# V2_SkyLight.net
KiCad netlist of a schematic drawn in Altium Designer
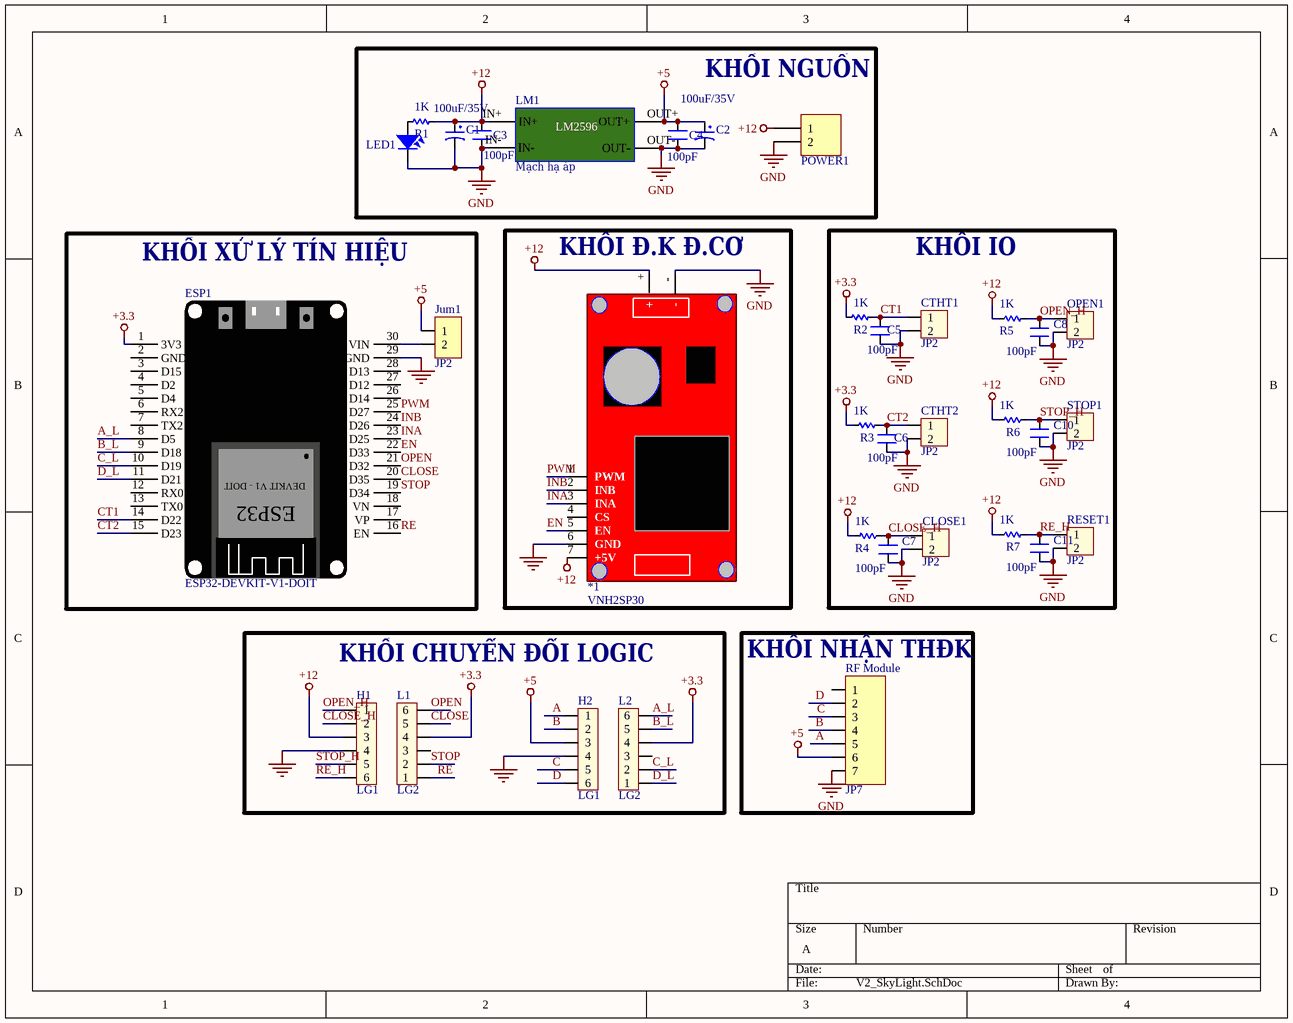
[diagram p0: V2_SkyLight.SchDoc]

(export (version "E")
  (design (tool "Eeschema 10.0.6"))
  (components
    (comp (ref "*1")
      (value "VNH2SP30")
      (footprint "VNH2SP30")
      (libsource (lib "Nhuphung_Main") (part "VNH2SP30"))
    )
    (comp (ref "C1")
      (value "100uF/35V")
      (footprint "CP1.5/3.4")
      (description "Cap 100uF/35V - 470uF/16V")
      (libsource (lib "syhaunguyen") (part "CP3"))
    )
    (comp (ref "C2")
      (value "100uF/35V")
      (footprint "CP1.5/3.4")
      (description "Cap 100uF/35V - 470uF/16V")
      (libsource (lib "syhaunguyen") (part "CP3"))
    )
    (comp (ref "C3")
      (value "100pF")
      (footprint "CN1")
      (description "Cap np  1pF - 472pF")
      (libsource (lib "syhaunguyen") (part "CN1"))
    )
    (comp (ref "C4")
      (value "100pF")
      (footprint "CN1")
      (description "Cap np  1pF - 472pF")
      (libsource (lib "syhaunguyen") (part "CN1"))
    )
    (comp (ref "C5")
      (value "100pF")
      (footprint "CN1")
      (description "Cap np  1pF - 472pF")
      (libsource (lib "syhaunguyen") (part "CN1"))
    )
    (comp (ref "C6")
      (value "100pF")
      (footprint "CN1")
      (description "Cap np  1pF - 472pF")
      (libsource (lib "syhaunguyen") (part "CN1"))
    )
    (comp (ref "C7")
      (value "100pF")
      (footprint "CN1")
      (description "Cap np  1pF - 472pF")
      (libsource (lib "syhaunguyen") (part "CN1"))
    )
    (comp (ref "C8")
      (value "100pF")
      (footprint "CN1")
      (description "Cap np  1pF - 472pF")
      (libsource (lib "syhaunguyen") (part "CN1"))
    )
    (comp (ref "C10")
      (value "100pF")
      (footprint "CN1")
      (description "Cap np  1pF - 472pF")
      (libsource (lib "syhaunguyen") (part "CN1"))
    )
    (comp (ref "C11")
      (value "100pF")
      (footprint "CN1")
      (description "Cap np  1pF - 472pF")
      (libsource (lib "syhaunguyen") (part "CN1"))
    )
    (comp (ref "CLOSE1")
      (value "JP2")
      (footprint "CON2")
      (description "Connector 2")
      (libsource (lib "syhaunguyen") (part "Con2"))
    )
    (comp (ref "CTHT1")
      (value "JP2")
      (footprint "CON2")
      (description "Connector 2")
      (libsource (lib "syhaunguyen") (part "Con2"))
    )
    (comp (ref "CTHT2")
      (value "JP2")
      (footprint "CON2")
      (description "Connector 2")
      (libsource (lib "syhaunguyen") (part "Con2"))
    )
    (comp (ref "ESP1")
      (value "ESP32-DEVKIT-V1-DOIT")
      (footprint "ESP32-WROOM-32")
      (libsource (lib "Nhuphung_Main") (part "ESP32-DEVKIT-V1-DOIT"))
    )
    (comp (ref "H1")
      (value "LG1")
      (footprint "JP6")
      (description "JP6 PIN")
      (libsource (lib "syhaunguyen") (part "JP6"))
    )
    (comp (ref "H2")
      (value "LG1")
      (footprint "JP6")
      (description "JP6 PIN")
      (libsource (lib "syhaunguyen") (part "JP6"))
    )
    (comp (ref "Jum1")
      (value "JP2")
      (footprint "JP2-CLOSED")
      (description "WR-PHD 2.54 mm Angled Socket Header")
      (fields
        (field (name "MANUFACTURER") "Würth Elektronik eiSos GmbH")
        (field (name "PARTNO") "613002143121")
        (field (name "CREATED BY") "Karrer Zheng")
      )
      (libsource (lib "LIBRARY (1)") (part "JP2"))
    )
    (comp (ref "L1")
      (value "LG2")
      (footprint "JP6")
      (description "JP6 PIN")
      (libsource (lib "") (part "JP6_1"))
    )
    (comp (ref "L2")
      (value "LG2")
      (footprint "JP6")
      (description "JP6 PIN")
      (libsource (lib "") (part "JP6_1"))
    )
    (comp (ref "LED1")
      (value "LED")
      (footprint "LED-5-RED")
      (description "LED Single colour Green and Red")
      (libsource (lib "LIBRARY (1)") (part "LED"))
    )
    (comp (ref "LM1")
      (value "Mạch hạ áp")
      (footprint "LM2596")
      (libsource (lib "Nhuphung_Main") (part "LM2596"))
    )
    (comp (ref "OPEN1")
      (value "JP2")
      (footprint "CON2")
      (description "Connector 2")
      (libsource (lib "syhaunguyen") (part "Con2"))
    )
    (comp (ref "POWER1")
      (value "Header 2_1")
      (footprint "HED2")
      (description "Header, 2-Pin")
      (fields (field (name "MANUFACTURER") "Generic Components"))
      (libsource (lib "syhaunguyen") (part "Header 2_1"))
    )
    (comp (ref "R1")
      (value "1K")
      (footprint "RES-1/4W-SMALL")
      (description "Res")
      (fields
        (field (name "MANUFACTURER") "Generic Components")
        (field (name "PUBLISHER") "Altium Hobart Technology Centre")
      )
      (libsource (lib "LIBRARY") (part "Res"))
    )
    (comp (ref "R2")
      (value "1K")
      (footprint "RES-1/4W-SMALL")
      (description "Res")
      (fields
        (field (name "MANUFACTURER") "Generic Components")
        (field (name "PUBLISHER") "Altium Hobart Technology Centre")
      )
      (libsource (lib "LIBRARY") (part "Res"))
    )
    (comp (ref "R3")
      (value "1K")
      (footprint "RES-1/4W-SMALL")
      (description "Res")
      (fields
        (field (name "MANUFACTURER") "Generic Components")
        (field (name "PUBLISHER") "Altium Hobart Technology Centre")
      )
      (libsource (lib "LIBRARY") (part "Res"))
    )
    (comp (ref "R4")
      (value "1K")
      (footprint "RES-1/4W-SMALL")
      (description "Res")
      (fields
        (field (name "MANUFACTURER") "Generic Components")
        (field (name "PUBLISHER") "Altium Hobart Technology Centre")
      )
      (libsource (lib "LIBRARY") (part "Res"))
    )
    (comp (ref "R5")
      (value "1K")
      (footprint "RES-1/4W-SMALL")
      (description "Res")
      (fields
        (field (name "MANUFACTURER") "Generic Components")
        (field (name "PUBLISHER") "Altium Hobart Technology Centre")
      )
      (libsource (lib "LIBRARY") (part "Res"))
    )
    (comp (ref "R6")
      (value "1K")
      (footprint "RES-1/4W-SMALL")
      (description "Res")
      (fields
        (field (name "MANUFACTURER") "Generic Components")
        (field (name "PUBLISHER") "Altium Hobart Technology Centre")
      )
      (libsource (lib "LIBRARY") (part "Res"))
    )
    (comp (ref "R7")
      (value "1K")
      (footprint "RES-1/4W-SMALL")
      (description "Res")
      (fields
        (field (name "MANUFACTURER") "Generic Components")
        (field (name "PUBLISHER") "Altium Hobart Technology Centre")
      )
      (libsource (lib "LIBRARY") (part "Res"))
    )
    (comp (ref "RESET1")
      (value "JP2")
      (footprint "CON2")
      (description "Connector 2")
      (libsource (lib "syhaunguyen") (part "Con2"))
    )
    (comp (ref "RF Module")
      (value "JP7")
      (footprint "JP7-C1T")
      (description "WR-PHD 2.54 mm Angled Socket Header")
      (fields
        (field (name "MANUFACTURER") "Würth Elektronik eiSos GmbH")
        (field (name "PARTNO") "613007143121")
        (field (name "CREATED BY") "Karrer Zheng")
      )
      (libsource (lib "LIBRARY (1)") (part "JP7"))
    )
    (comp (ref "STOP1")
      (value "JP2")
      (footprint "CON2")
      (description "Connector 2")
      (libsource (lib "syhaunguyen") (part "Con2"))
    )
  )
  (nets
    (net (code "1") (name "+3.3") (class "Default")
      (node (ref "ESP1") (pin "1") (pinfunction "3V3_1") (pintype "passive"))
      (node (ref "L1") (pin "4") (pinfunction "4_4") (pintype "passive"))
      (node (ref "L2") (pin "4") (pinfunction "4_4") (pintype "passive"))
      (node (ref "R2") (pin "1") (pinfunction "1_1") (pintype "passive"))
      (node (ref "R3") (pin "1") (pinfunction "1_1") (pintype "passive"))
    )
    (net (code "2") (name "+5") (class "Default")
      (node (ref "C2") (pin "1") (pinfunction "1_1") (pintype "passive"))
      (node (ref "C4") (pin "2") (pinfunction "2_2") (pintype "passive"))
      (node (ref "H2") (pin "3") (pinfunction "3_3") (pintype "passive"))
      (node (ref "Jum1") (pin "1") (pinfunction "1_1") (pintype "passive"))
      (node (ref "LM1") (pin "OUT+") (pinfunction "OUT+_OUT+") (pintype "passive"))
      (node (ref "RF Module") (pin "6") (pinfunction "6_6") (pintype "passive"))
    )
    (net (code "3") (name "+12") (class "Default")
      (node (ref "*1") (pin "+") (pinfunction "+_+") (pintype "passive"))
      (node (ref "*1") (pin "7") (pinfunction "+5V_7") (pintype "passive"))
      (node (ref "C1") (pin "1") (pinfunction "1_1") (pintype "passive"))
      (node (ref "C3") (pin "2") (pinfunction "2_2") (pintype "passive"))
      (node (ref "H1") (pin "3") (pinfunction "3_3") (pintype "passive"))
      (node (ref "LM1") (pin "IN+") (pinfunction "IN+_IN+") (pintype "passive"))
      (node (ref "POWER1") (pin "1") (pinfunction "1_1") (pintype "passive"))
      (node (ref "R1") (pin "2") (pinfunction "2_2") (pintype "passive"))
      (node (ref "R4") (pin "1") (pinfunction "1_1") (pintype "passive"))
      (node (ref "R5") (pin "1") (pinfunction "1_1") (pintype "passive"))
      (node (ref "R6") (pin "1") (pinfunction "1_1") (pintype "passive"))
      (node (ref "R7") (pin "1") (pinfunction "1_1") (pintype "passive"))
    )
    (net (code "4") (name "/A") (class "Default")
      (node (ref "H2") (pin "1") (pinfunction "1_1") (pintype "passive"))
      (node (ref "RF Module") (pin "5") (pinfunction "5_5") (pintype "passive"))
    )
    (net (code "5") (name "/A_L") (class "Default")
      (node (ref "ESP1") (pin "8") (pinfunction "D5_8") (pintype "passive"))
      (node (ref "L2") (pin "6") (pinfunction "6_6") (pintype "passive"))
    )
    (net (code "6") (name "/B") (class "Default")
      (node (ref "H2") (pin "2") (pinfunction "2_2") (pintype "passive"))
      (node (ref "RF Module") (pin "4") (pinfunction "4_4") (pintype "passive"))
    )
    (net (code "7") (name "/B_L") (class "Default")
      (node (ref "ESP1") (pin "9") (pinfunction "D18_9") (pintype "passive"))
      (node (ref "L2") (pin "5") (pinfunction "5_5") (pintype "passive"))
    )
    (net (code "8") (name "/C") (class "Default")
      (node (ref "H2") (pin "5") (pinfunction "5_5") (pintype "passive"))
      (node (ref "RF Module") (pin "3") (pinfunction "3_3") (pintype "passive"))
    )
    (net (code "9") (name "/CLOSE") (class "Default")
      (node (ref "ESP1") (pin "20") (pinfunction "D35_20") (pintype "passive"))
      (node (ref "L1") (pin "5") (pinfunction "5_5") (pintype "passive"))
    )
    (net (code "10") (name "/CLOSE_H") (class "Default")
      (node (ref "C7") (pin "2") (pinfunction "2_2") (pintype "passive"))
      (node (ref "CLOSE1") (pin "1") (pinfunction "1_1") (pintype "passive"))
      (node (ref "H1") (pin "2") (pinfunction "2_2") (pintype "passive"))
      (node (ref "R4") (pin "2") (pinfunction "2_2") (pintype "passive"))
    )
    (net (code "11") (name "/CT1") (class "Default")
      (node (ref "C5") (pin "2") (pinfunction "2_2") (pintype "passive"))
      (node (ref "CTHT1") (pin "1") (pinfunction "1_1") (pintype "passive"))
      (node (ref "ESP1") (pin "14") (pinfunction "D22_14") (pintype "passive"))
      (node (ref "R2") (pin "2") (pinfunction "2_2") (pintype "passive"))
    )
    (net (code "12") (name "/CT2") (class "Default")
      (node (ref "C6") (pin "2") (pinfunction "2_2") (pintype "passive"))
      (node (ref "CTHT2") (pin "1") (pinfunction "1_1") (pintype "passive"))
      (node (ref "ESP1") (pin "15") (pinfunction "D23_15") (pintype "passive"))
      (node (ref "R3") (pin "2") (pinfunction "2_2") (pintype "passive"))
    )
    (net (code "13") (name "/C_L") (class "Default")
      (node (ref "ESP1") (pin "10") (pinfunction "D19_10") (pintype "passive"))
      (node (ref "L2") (pin "2") (pinfunction "2_2") (pintype "passive"))
    )
    (net (code "14") (name "/D") (class "Default")
      (node (ref "H2") (pin "6") (pinfunction "6_6") (pintype "passive"))
      (node (ref "RF Module") (pin "2") (pinfunction "2_2") (pintype "passive"))
    )
    (net (code "15") (name "/D_L") (class "Default")
      (node (ref "ESP1") (pin "11") (pinfunction "D21_11") (pintype "passive"))
      (node (ref "L2") (pin "1") (pinfunction "1_1") (pintype "passive"))
    )
    (net (code "16") (name "/EN") (class "Default")
      (node (ref "*1") (pin "5") (pinfunction "EN_5") (pintype "passive"))
      (node (ref "ESP1") (pin "22") (pinfunction "D33_22") (pintype "passive"))
    )
    (net (code "17") (name "/INA") (class "Default")
      (node (ref "*1") (pin "3") (pinfunction "INA_3") (pintype "passive"))
      (node (ref "ESP1") (pin "23") (pinfunction "D25_23") (pintype "passive"))
    )
    (net (code "18") (name "/INB") (class "Default")
      (node (ref "*1") (pin "2") (pinfunction "INB_2") (pintype "passive"))
      (node (ref "ESP1") (pin "24") (pinfunction "D26_24") (pintype "passive"))
    )
    (net (code "19") (name "/OPEN") (class "Default")
      (node (ref "ESP1") (pin "21") (pinfunction "D32_21") (pintype "passive"))
      (node (ref "L1") (pin "6") (pinfunction "6_6") (pintype "passive"))
    )
    (net (code "20") (name "/OPEN_H") (class "Default")
      (node (ref "C8") (pin "2") (pinfunction "2_2") (pintype "passive"))
      (node (ref "H1") (pin "1") (pinfunction "1_1") (pintype "passive"))
      (node (ref "OPEN1") (pin "1") (pinfunction "1_1") (pintype "passive"))
      (node (ref "R5") (pin "2") (pinfunction "2_2") (pintype "passive"))
    )
    (net (code "21") (name "/PWM") (class "Default")
      (node (ref "*1") (pin "1") (pinfunction "PWM_1") (pintype "passive"))
      (node (ref "ESP1") (pin "25") (pinfunction "D27_25") (pintype "passive"))
    )
    (net (code "22") (name "/RE") (class "Default")
      (node (ref "ESP1") (pin "16") (pinfunction "EN_16") (pintype "passive"))
      (node (ref "L1") (pin "1") (pinfunction "1_1") (pintype "passive"))
    )
    (net (code "23") (name "/RE_H") (class "Default")
      (node (ref "C11") (pin "2") (pinfunction "2_2") (pintype "passive"))
      (node (ref "H1") (pin "6") (pinfunction "6_6") (pintype "passive"))
      (node (ref "R7") (pin "2") (pinfunction "2_2") (pintype "passive"))
      (node (ref "RESET1") (pin "1") (pinfunction "1_1") (pintype "passive"))
    )
    (net (code "24") (name "/STOP") (class "Default")
      (node (ref "ESP1") (pin "19") (pinfunction "D34_19") (pintype "passive"))
      (node (ref "L1") (pin "2") (pinfunction "2_2") (pintype "passive"))
    )
    (net (code "25") (name "/STOP_H") (class "Default")
      (node (ref "C10") (pin "2") (pinfunction "2_2") (pintype "passive"))
      (node (ref "H1") (pin "5") (pinfunction "5_5") (pintype "passive"))
      (node (ref "R6") (pin "2") (pinfunction "2_2") (pintype "passive"))
      (node (ref "STOP1") (pin "1") (pinfunction "1_1") (pintype "passive"))
    )
    (net (code "26") (name "GND") (class "Default")
      (node (ref "*1") (pin "-") (pinfunction "-_-") (pintype "passive"))
      (node (ref "*1") (pin "6") (pinfunction "GND_6") (pintype "passive"))
      (node (ref "C1") (pin "2") (pinfunction "2_2") (pintype "passive"))
      (node (ref "C10") (pin "1") (pinfunction "1_1") (pintype "passive"))
      (node (ref "C11") (pin "1") (pinfunction "1_1") (pintype "passive"))
      (node (ref "C2") (pin "2") (pinfunction "2_2") (pintype "passive"))
      (node (ref "C3") (pin "1") (pinfunction "1_1") (pintype "passive"))
      (node (ref "C4") (pin "1") (pinfunction "1_1") (pintype "passive"))
      (node (ref "C5") (pin "1") (pinfunction "1_1") (pintype "passive"))
      (node (ref "C6") (pin "1") (pinfunction "1_1") (pintype "passive"))
      (node (ref "C7") (pin "1") (pinfunction "1_1") (pintype "passive"))
      (node (ref "C8") (pin "1") (pinfunction "1_1") (pintype "passive"))
      (node (ref "CLOSE1") (pin "2") (pinfunction "2_2") (pintype "passive"))
      (node (ref "CTHT1") (pin "2") (pinfunction "2_2") (pintype "passive"))
      (node (ref "CTHT2") (pin "2") (pinfunction "2_2") (pintype "passive"))
      (node (ref "ESP1") (pin "29") (pinfunction "GND_29") (pintype "passive"))
      (node (ref "H1") (pin "4") (pinfunction "4_4") (pintype "passive"))
      (node (ref "H2") (pin "4") (pinfunction "4_4") (pintype "passive"))
      (node (ref "LED1") (pin "2") (pinfunction "2_2") (pintype "passive"))
      (node (ref "LM1") (pin "IN-") (pinfunction "IN-_IN-") (pintype "passive"))
      (node (ref "LM1") (pin "OUT-") (pinfunction "OUT-_OUT-") (pintype "passive"))
      (node (ref "OPEN1") (pin "2") (pinfunction "2_2") (pintype "passive"))
      (node (ref "POWER1") (pin "2") (pinfunction "2_2") (pintype "passive"))
      (node (ref "RESET1") (pin "2") (pinfunction "2_2") (pintype "passive"))
      (node (ref "RF Module") (pin "7") (pinfunction "7_7") (pintype "passive"))
      (node (ref "STOP1") (pin "2") (pinfunction "2_2") (pintype "passive"))
    )
    (net (code "27") (name "Net-(ESP1-VIN)") (class "Default")
      (node (ref "ESP1") (pin "30") (pinfunction "VIN_30") (pintype "passive"))
      (node (ref "Jum1") (pin "2") (pinfunction "2_2") (pintype "passive"))
    )
    (net (code "28") (name "Net-(LED1-Pad1)") (class "Default")
      (node (ref "LED1") (pin "1") (pinfunction "1_1") (pintype "passive"))
      (node (ref "R1") (pin "1") (pinfunction "1_1") (pintype "passive"))
    )
    (net (code "29") (name "unconnected-(*1-CS-Pad4)") (class "Default")
      (node (ref "*1") (pin "4") (pinfunction "CS_4") (pintype "passive"))
    )
    (net (code "30") (name "unconnected-(ESP1-D2-Pad4)") (class "Default")
      (node (ref "ESP1") (pin "4") (pinfunction "D2_4") (pintype "passive"))
    )
    (net (code "31") (name "unconnected-(ESP1-D4-Pad5)") (class "Default")
      (node (ref "ESP1") (pin "5") (pinfunction "D4_5") (pintype "passive"))
    )
    (net (code "32") (name "unconnected-(ESP1-D12-Pad27)") (class "Default")
      (node (ref "ESP1") (pin "27") (pinfunction "D12_27") (pintype "passive"))
    )
    (net (code "33") (name "unconnected-(ESP1-D13-Pad28)") (class "Default")
      (node (ref "ESP1") (pin "28") (pinfunction "D13_28") (pintype "passive"))
    )
    (net (code "34") (name "unconnected-(ESP1-D14-Pad26)") (class "Default")
      (node (ref "ESP1") (pin "26") (pinfunction "D14_26") (pintype "passive"))
    )
    (net (code "35") (name "unconnected-(ESP1-D15-Pad3)") (class "Default")
      (node (ref "ESP1") (pin "3") (pinfunction "D15_3") (pintype "passive"))
    )
    (net (code "36") (name "unconnected-(ESP1-GND-Pad2)") (class "Default")
      (node (ref "ESP1") (pin "2") (pinfunction "GND_2") (pintype "passive"))
    )
    (net (code "37") (name "unconnected-(ESP1-RX0-Pad12)") (class "Default")
      (node (ref "ESP1") (pin "12") (pinfunction "RX0_12") (pintype "passive"))
    )
    (net (code "38") (name "unconnected-(ESP1-RX2-Pad6)") (class "Default")
      (node (ref "ESP1") (pin "6") (pinfunction "RX2_6") (pintype "passive"))
    )
    (net (code "39") (name "unconnected-(ESP1-TX0-Pad13)") (class "Default")
      (node (ref "ESP1") (pin "13") (pinfunction "TX0_13") (pintype "passive"))
    )
    (net (code "40") (name "unconnected-(ESP1-TX2-Pad7)") (class "Default")
      (node (ref "ESP1") (pin "7") (pinfunction "TX2_7") (pintype "passive"))
    )
    (net (code "41") (name "unconnected-(ESP1-VN-Pad18)") (class "Default")
      (node (ref "ESP1") (pin "18") (pinfunction "VN_18") (pintype "passive"))
    )
    (net (code "42") (name "unconnected-(ESP1-VP-Pad17)") (class "Default")
      (node (ref "ESP1") (pin "17") (pinfunction "VP_17") (pintype "passive"))
    )
    (net (code "43") (name "unconnected-(L1-Pad3)") (class "Default")
      (node (ref "L1") (pin "3") (pinfunction "3_3") (pintype "passive"))
    )
    (net (code "44") (name "unconnected-(L2-Pad3)") (class "Default")
      (node (ref "L2") (pin "3") (pinfunction "3_3") (pintype "passive"))
    )
    (net (code "45") (name "unconnected-(RF Module-Pad1)") (class "Default")
      (node (ref "RF Module") (pin "1") (pinfunction "1_1") (pintype "passive"))
    )
  )
)
